# Processor-2.net
KiCad netlist of a schematic drawn in Altium Designer
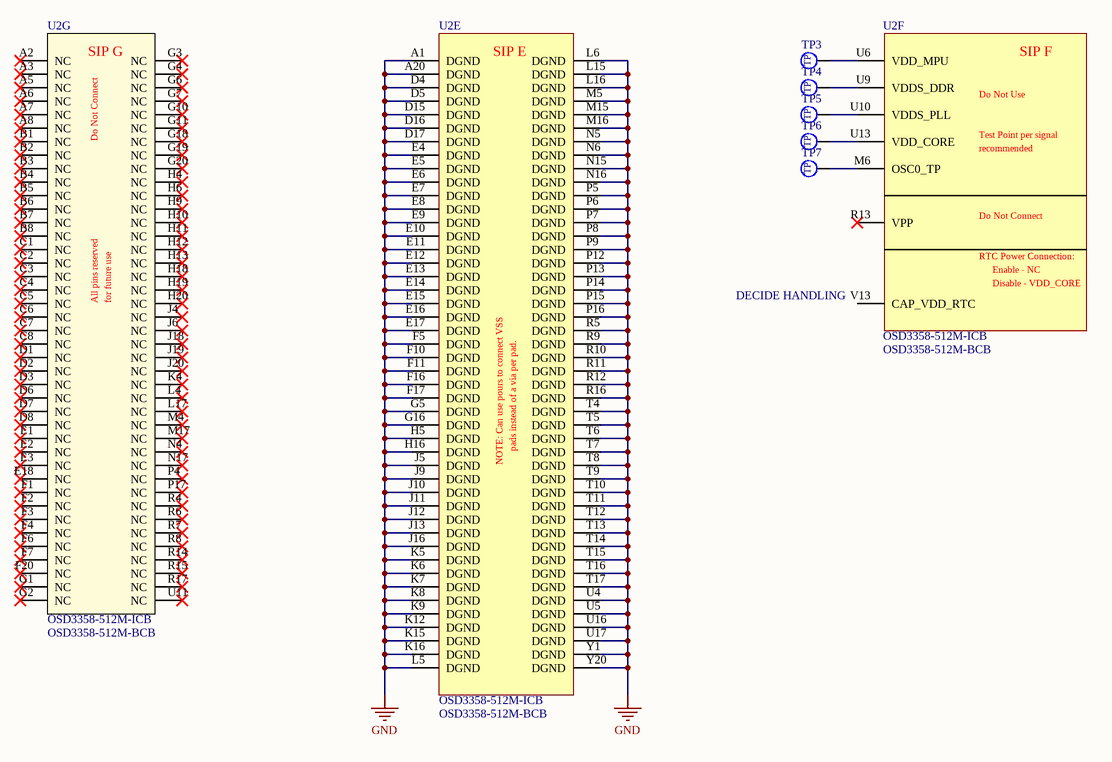
[diagram p0: Processor-2.SchDoc]

(export (version "E")
  (design (tool "Eeschema 10.0.6"))
  (components
    (comp (ref "TP3")
      (value "2.5mm_SMD_TestPoint")
      (footprint "2.5mm TestPoint")
      (libsource (lib "HAB_Components") (part "2.5mm_SMD_TestPoint"))
    )
    (comp (ref "TP4")
      (value "2.5mm_SMD_TestPoint")
      (footprint "2.5mm TestPoint")
      (libsource (lib "HAB_Components") (part "2.5mm_SMD_TestPoint"))
    )
    (comp (ref "TP5")
      (value "2.5mm_SMD_TestPoint")
      (footprint "2.5mm TestPoint")
      (libsource (lib "HAB_Components") (part "2.5mm_SMD_TestPoint"))
    )
    (comp (ref "TP6")
      (value "2.5mm_SMD_TestPoint")
      (footprint "2.5mm TestPoint")
      (libsource (lib "HAB_Components") (part "2.5mm_SMD_TestPoint"))
    )
    (comp (ref "TP7")
      (value "2.5mm_SMD_TestPoint")
      (footprint "2.5mm TestPoint")
      (libsource (lib "HAB_Components") (part "2.5mm_SMD_TestPoint"))
    )
    (comp (ref "U2")
      (value "OSD3358-512M-ICB")
      (footprint "BGA_20x20_400_1p27mm")
      (fields (field (name "MANUFACTURER") "Octavo Systems") (field (name "PARTNUMBER") "OSD3358-512M-BCB"))
      (libsource (lib "OctavoLib") (part "OSD3358-512M-ICB"))
    )
  )
  (nets
    (net (code "1") (name "GND") (class "Default")
      (node (ref "U2") (pin "A1") (pinfunction "DGND_A1") (pintype "power_in"))
      (node (ref "U2") (pin "A20") (pinfunction "DGND_A20") (pintype "power_in"))
      (node (ref "U2") (pin "D15") (pinfunction "DGND_D15") (pintype "power_in"))
      (node (ref "U2") (pin "D16") (pinfunction "DGND_D16") (pintype "power_in"))
      (node (ref "U2") (pin "D17") (pinfunction "DGND_D17") (pintype "power_in"))
      (node (ref "U2") (pin "D4") (pinfunction "DGND_D4") (pintype "power_in"))
      (node (ref "U2") (pin "D5") (pinfunction "DGND_D5") (pintype "power_in"))
      (node (ref "U2") (pin "E10") (pinfunction "DGND_E10") (pintype "power_in"))
      (node (ref "U2") (pin "E11") (pinfunction "DGND_E11") (pintype "power_in"))
      (node (ref "U2") (pin "E12") (pinfunction "DGND_E12") (pintype "power_in"))
      (node (ref "U2") (pin "E13") (pinfunction "DGND_E13") (pintype "power_in"))
      (node (ref "U2") (pin "E14") (pinfunction "DGND_E14") (pintype "power_in"))
      (node (ref "U2") (pin "E15") (pinfunction "DGND_E15") (pintype "power_in"))
      (node (ref "U2") (pin "E16") (pinfunction "DGND_E16") (pintype "power_in"))
      (node (ref "U2") (pin "E17") (pinfunction "DGND_E17") (pintype "power_in"))
      (node (ref "U2") (pin "E4") (pinfunction "DGND_E4") (pintype "power_in"))
      (node (ref "U2") (pin "E5") (pinfunction "DGND_E5") (pintype "power_in"))
      (node (ref "U2") (pin "E6") (pinfunction "DGND_E6") (pintype "power_in"))
      (node (ref "U2") (pin "E7") (pinfunction "DGND_E7") (pintype "power_in"))
      (node (ref "U2") (pin "E8") (pinfunction "DGND_E8") (pintype "power_in"))
      (node (ref "U2") (pin "E9") (pinfunction "DGND_E9") (pintype "power_in"))
      (node (ref "U2") (pin "F10") (pinfunction "DGND_F10") (pintype "power_in"))
      (node (ref "U2") (pin "F11") (pinfunction "DGND_F11") (pintype "power_in"))
      (node (ref "U2") (pin "F16") (pinfunction "DGND_F16") (pintype "power_in"))
      (node (ref "U2") (pin "F17") (pinfunction "DGND_F17") (pintype "power_in"))
      (node (ref "U2") (pin "F5") (pinfunction "DGND_F5") (pintype "power_in"))
      (node (ref "U2") (pin "G16") (pinfunction "DGND_G16") (pintype "power_in"))
      (node (ref "U2") (pin "G5") (pinfunction "DGND_G5") (pintype "power_in"))
      (node (ref "U2") (pin "H16") (pinfunction "DGND_H16") (pintype "power_in"))
      (node (ref "U2") (pin "H5") (pinfunction "DGND_H5") (pintype "power_in"))
      (node (ref "U2") (pin "J10") (pinfunction "DGND_J10") (pintype "power_in"))
      (node (ref "U2") (pin "J11") (pinfunction "DGND_J11") (pintype "power_in"))
      (node (ref "U2") (pin "J12") (pinfunction "DGND_J12") (pintype "power_in"))
      (node (ref "U2") (pin "J13") (pinfunction "DGND_J13") (pintype "power_in"))
      (node (ref "U2") (pin "J16") (pinfunction "DGND_J16") (pintype "power_in"))
      (node (ref "U2") (pin "J5") (pinfunction "DGND_J5") (pintype "power_in"))
      (node (ref "U2") (pin "J9") (pinfunction "DGND_J9") (pintype "power_in"))
      (node (ref "U2") (pin "K12") (pinfunction "DGND_K12") (pintype "power_in"))
      (node (ref "U2") (pin "K15") (pinfunction "DGND_K15") (pintype "power_in"))
      (node (ref "U2") (pin "K16") (pinfunction "DGND_K16") (pintype "power_in"))
      (node (ref "U2") (pin "K5") (pinfunction "DGND_K5") (pintype "power_in"))
      (node (ref "U2") (pin "K6") (pinfunction "DGND_K6") (pintype "power_in"))
      (node (ref "U2") (pin "K7") (pinfunction "DGND_K7") (pintype "power_in"))
      (node (ref "U2") (pin "K8") (pinfunction "DGND_K8") (pintype "power_in"))
      (node (ref "U2") (pin "K9") (pinfunction "DGND_K9") (pintype "power_in"))
      (node (ref "U2") (pin "L15") (pinfunction "DGND_L15") (pintype "power_in"))
      (node (ref "U2") (pin "L16") (pinfunction "DGND_L16") (pintype "power_in"))
      (node (ref "U2") (pin "L5") (pinfunction "DGND_L5") (pintype "power_in"))
      (node (ref "U2") (pin "L6") (pinfunction "DGND_L6") (pintype "power_in"))
      (node (ref "U2") (pin "M15") (pinfunction "DGND_M15") (pintype "power_in"))
      (node (ref "U2") (pin "M16") (pinfunction "DGND_M16") (pintype "power_in"))
      (node (ref "U2") (pin "M5") (pinfunction "DGND_M5") (pintype "power_in"))
      (node (ref "U2") (pin "N15") (pinfunction "DGND_N15") (pintype "power_in"))
      (node (ref "U2") (pin "N16") (pinfunction "DGND_N16") (pintype "power_in"))
      (node (ref "U2") (pin "N5") (pinfunction "DGND_N5") (pintype "power_in"))
      (node (ref "U2") (pin "N6") (pinfunction "DGND_N6") (pintype "power_in"))
      (node (ref "U2") (pin "P12") (pinfunction "DGND_P12") (pintype "power_in"))
      (node (ref "U2") (pin "P13") (pinfunction "DGND_P13") (pintype "power_in"))
      (node (ref "U2") (pin "P14") (pinfunction "DGND_P14") (pintype "power_in"))
      (node (ref "U2") (pin "P15") (pinfunction "DGND_P15") (pintype "power_in"))
      (node (ref "U2") (pin "P16") (pinfunction "DGND_P16") (pintype "power_in"))
      (node (ref "U2") (pin "P5") (pinfunction "DGND_P5") (pintype "power_in"))
      (node (ref "U2") (pin "P6") (pinfunction "DGND_P6") (pintype "power_in"))
      (node (ref "U2") (pin "P7") (pinfunction "DGND_P7") (pintype "power_in"))
      (node (ref "U2") (pin "P8") (pinfunction "DGND_P8") (pintype "power_in"))
      (node (ref "U2") (pin "P9") (pinfunction "DGND_P9") (pintype "power_in"))
      (node (ref "U2") (pin "R10") (pinfunction "DGND_R10") (pintype "power_in"))
      (node (ref "U2") (pin "R11") (pinfunction "DGND_R11") (pintype "power_in"))
      (node (ref "U2") (pin "R12") (pinfunction "DGND_R12") (pintype "power_in"))
      (node (ref "U2") (pin "R16") (pinfunction "DGND_R16") (pintype "power_in"))
      (node (ref "U2") (pin "R5") (pinfunction "DGND_R5") (pintype "power_in"))
      (node (ref "U2") (pin "R9") (pinfunction "DGND_R9") (pintype "power_in"))
      (node (ref "U2") (pin "T10") (pinfunction "DGND_T10") (pintype "power_in"))
      (node (ref "U2") (pin "T11") (pinfunction "DGND_T11") (pintype "power_in"))
      (node (ref "U2") (pin "T12") (pinfunction "DGND_T12") (pintype "power_in"))
      (node (ref "U2") (pin "T13") (pinfunction "DGND_T13") (pintype "power_in"))
      (node (ref "U2") (pin "T14") (pinfunction "DGND_T14") (pintype "power_in"))
      (node (ref "U2") (pin "T15") (pinfunction "DGND_T15") (pintype "power_in"))
      (node (ref "U2") (pin "T16") (pinfunction "DGND_T16") (pintype "power_in"))
      (node (ref "U2") (pin "T17") (pinfunction "DGND_T17") (pintype "power_in"))
      (node (ref "U2") (pin "T4") (pinfunction "DGND_T4") (pintype "power_in"))
      (node (ref "U2") (pin "T5") (pinfunction "DGND_T5") (pintype "power_in"))
      (node (ref "U2") (pin "T6") (pinfunction "DGND_T6") (pintype "power_in"))
      (node (ref "U2") (pin "T7") (pinfunction "DGND_T7") (pintype "power_in"))
      (node (ref "U2") (pin "T8") (pinfunction "DGND_T8") (pintype "power_in"))
      (node (ref "U2") (pin "T9") (pinfunction "DGND_T9") (pintype "power_in"))
      (node (ref "U2") (pin "U16") (pinfunction "DGND_U16") (pintype "power_in"))
      (node (ref "U2") (pin "U17") (pinfunction "DGND_U17") (pintype "power_in"))
      (node (ref "U2") (pin "U4") (pinfunction "DGND_U4") (pintype "power_in"))
      (node (ref "U2") (pin "U5") (pinfunction "DGND_U5") (pintype "power_in"))
      (node (ref "U2") (pin "Y1") (pinfunction "DGND_Y1") (pintype "power_in"))
      (node (ref "U2") (pin "Y20") (pinfunction "DGND_Y20") (pintype "power_in"))
    )
    (net (code "2") (name "Net-(U2F-OSC0_TP)") (class "Default")
      (node (ref "TP7") (pin "1") (pintype "passive"))
      (node (ref "U2") (pin "M6") (pinfunction "OSC0_TP_M6") (pintype "passive"))
    )
    (net (code "3") (name "Net-(U2F-VDDS_DDR)") (class "Default")
      (node (ref "TP4") (pin "1") (pintype "passive"))
      (node (ref "U2") (pin "U9") (pinfunction "VDDS_DDR_U9") (pintype "power_in"))
    )
    (net (code "4") (name "Net-(U2F-VDDS_PLL)") (class "Default")
      (node (ref "TP5") (pin "1") (pintype "passive"))
      (node (ref "U2") (pin "U10") (pinfunction "VDDS_PLL_U10") (pintype "power_in"))
    )
    (net (code "5") (name "Net-(U2F-VDD_CORE)") (class "Default")
      (node (ref "TP6") (pin "1") (pintype "passive"))
      (node (ref "U2") (pin "U13") (pinfunction "VDD_CORE_U13") (pintype "power_in"))
    )
    (net (code "6") (name "Net-(U2F-VDD_MPU)") (class "Default")
      (node (ref "TP3") (pin "1") (pintype "passive"))
      (node (ref "U2") (pin "U6") (pinfunction "VDD_MPU_U6") (pintype "power_in"))
    )
    (net (code "7") (name "unconnected-(U2F-CAP_VDD_RTC-PadV13)") (class "Default")
      (node (ref "U2") (pin "V13") (pinfunction "CAP_VDD_RTC_V13") (pintype "power_in"))
    )
    (net (code "8") (name "unconnected-(U2F-VPP-PadR13)") (class "Default")
      (node (ref "U2") (pin "R13") (pinfunction "VPP_R13") (pintype "power_in+no_connect"))
    )
    (net (code "9") (name "unconnected-(U2G-NC-PadA2)") (class "Default")
      (node (ref "U2") (pin "A2") (pinfunction "NC_A2") (pintype "passive+no_connect"))
    )
    (net (code "10") (name "unconnected-(U2G-NC-PadA3)") (class "Default")
      (node (ref "U2") (pin "A3") (pinfunction "NC_A3") (pintype "passive+no_connect"))
    )
    (net (code "11") (name "unconnected-(U2G-NC-PadA5)") (class "Default")
      (node (ref "U2") (pin "A5") (pinfunction "NC_A5") (pintype "passive+no_connect"))
    )
    (net (code "12") (name "unconnected-(U2G-NC-PadA6)") (class "Default")
      (node (ref "U2") (pin "A6") (pinfunction "NC_A6") (pintype "passive+no_connect"))
    )
    (net (code "13") (name "unconnected-(U2G-NC-PadA7)") (class "Default")
      (node (ref "U2") (pin "A7") (pinfunction "NC_A7") (pintype "passive+no_connect"))
    )
    (net (code "14") (name "unconnected-(U2G-NC-PadA8)") (class "Default")
      (node (ref "U2") (pin "A8") (pinfunction "NC_A8") (pintype "passive+no_connect"))
    )
    (net (code "15") (name "unconnected-(U2G-NC-PadB1)") (class "Default")
      (node (ref "U2") (pin "B1") (pinfunction "NC_B1") (pintype "passive+no_connect"))
    )
    (net (code "16") (name "unconnected-(U2G-NC-PadB2)") (class "Default")
      (node (ref "U2") (pin "B2") (pinfunction "NC_B2") (pintype "passive+no_connect"))
    )
    (net (code "17") (name "unconnected-(U2G-NC-PadB3)") (class "Default")
      (node (ref "U2") (pin "B3") (pinfunction "NC_B3") (pintype "passive+no_connect"))
    )
    (net (code "18") (name "unconnected-(U2G-NC-PadB4)") (class "Default")
      (node (ref "U2") (pin "B4") (pinfunction "NC_B4") (pintype "passive+no_connect"))
    )
    (net (code "19") (name "unconnected-(U2G-NC-PadB5)") (class "Default")
      (node (ref "U2") (pin "B5") (pinfunction "NC_B5") (pintype "passive+no_connect"))
    )
    (net (code "20") (name "unconnected-(U2G-NC-PadB6)") (class "Default")
      (node (ref "U2") (pin "B6") (pinfunction "NC_B6") (pintype "passive+no_connect"))
    )
    (net (code "21") (name "unconnected-(U2G-NC-PadB7)") (class "Default")
      (node (ref "U2") (pin "B7") (pinfunction "NC_B7") (pintype "passive+no_connect"))
    )
    (net (code "22") (name "unconnected-(U2G-NC-PadB8)") (class "Default")
      (node (ref "U2") (pin "B8") (pinfunction "NC_B8") (pintype "passive+no_connect"))
    )
    (net (code "23") (name "unconnected-(U2G-NC-PadC1)") (class "Default")
      (node (ref "U2") (pin "C1") (pinfunction "NC_C1") (pintype "passive+no_connect"))
    )
    (net (code "24") (name "unconnected-(U2G-NC-PadC2)") (class "Default")
      (node (ref "U2") (pin "C2") (pinfunction "NC_C2") (pintype "passive+no_connect"))
    )
    (net (code "25") (name "unconnected-(U2G-NC-PadC3)") (class "Default")
      (node (ref "U2") (pin "C3") (pinfunction "NC_C3") (pintype "passive+no_connect"))
    )
    (net (code "26") (name "unconnected-(U2G-NC-PadC4)") (class "Default")
      (node (ref "U2") (pin "C4") (pinfunction "NC_C4") (pintype "passive+no_connect"))
    )
    (net (code "27") (name "unconnected-(U2G-NC-PadC5)") (class "Default")
      (node (ref "U2") (pin "C5") (pinfunction "NC_C5") (pintype "passive+no_connect"))
    )
    (net (code "28") (name "unconnected-(U2G-NC-PadC6)") (class "Default")
      (node (ref "U2") (pin "C6") (pinfunction "NC_C6") (pintype "passive+no_connect"))
    )
    (net (code "29") (name "unconnected-(U2G-NC-PadC7)") (class "Default")
      (node (ref "U2") (pin "C7") (pinfunction "NC_C7") (pintype "passive+no_connect"))
    )
    (net (code "30") (name "unconnected-(U2G-NC-PadC8)") (class "Default")
      (node (ref "U2") (pin "C8") (pinfunction "NC_C8") (pintype "passive+no_connect"))
    )
    (net (code "31") (name "unconnected-(U2G-NC-PadD1)") (class "Default")
      (node (ref "U2") (pin "D1") (pinfunction "NC_D1") (pintype "passive+no_connect"))
    )
    (net (code "32") (name "unconnected-(U2G-NC-PadD2)") (class "Default")
      (node (ref "U2") (pin "D2") (pinfunction "NC_D2") (pintype "passive+no_connect"))
    )
    (net (code "33") (name "unconnected-(U2G-NC-PadD3)") (class "Default")
      (node (ref "U2") (pin "D3") (pinfunction "NC_D3") (pintype "passive+no_connect"))
    )
    (net (code "34") (name "unconnected-(U2G-NC-PadD6)") (class "Default")
      (node (ref "U2") (pin "D6") (pinfunction "NC_D6") (pintype "passive+no_connect"))
    )
    (net (code "35") (name "unconnected-(U2G-NC-PadD7)") (class "Default")
      (node (ref "U2") (pin "D7") (pinfunction "NC_D7") (pintype "passive+no_connect"))
    )
    (net (code "36") (name "unconnected-(U2G-NC-PadD8)") (class "Default")
      (node (ref "U2") (pin "D8") (pinfunction "NC_D8") (pintype "passive+no_connect"))
    )
    (net (code "37") (name "unconnected-(U2G-NC-PadE1)") (class "Default")
      (node (ref "U2") (pin "E1") (pinfunction "NC_E1") (pintype "passive+no_connect"))
    )
    (net (code "38") (name "unconnected-(U2G-NC-PadE2)") (class "Default")
      (node (ref "U2") (pin "E2") (pinfunction "NC_E2") (pintype "passive+no_connect"))
    )
    (net (code "39") (name "unconnected-(U2G-NC-PadE3)") (class "Default")
      (node (ref "U2") (pin "E3") (pinfunction "NC_E3") (pintype "passive+no_connect"))
    )
    (net (code "40") (name "unconnected-(U2G-NC-PadE18)") (class "Default")
      (node (ref "U2") (pin "E18") (pinfunction "NC_E18") (pintype "passive+no_connect"))
    )
    (net (code "41") (name "unconnected-(U2G-NC-PadF1)") (class "Default")
      (node (ref "U2") (pin "F1") (pinfunction "NC_F1") (pintype "passive+no_connect"))
    )
    (net (code "42") (name "unconnected-(U2G-NC-PadF2)") (class "Default")
      (node (ref "U2") (pin "F2") (pinfunction "NC_F2") (pintype "passive+no_connect"))
    )
    (net (code "43") (name "unconnected-(U2G-NC-PadF3)") (class "Default")
      (node (ref "U2") (pin "F3") (pinfunction "NC_F3") (pintype "passive+no_connect"))
    )
    (net (code "44") (name "unconnected-(U2G-NC-PadF4)") (class "Default")
      (node (ref "U2") (pin "F4") (pinfunction "NC_F4") (pintype "passive+no_connect"))
    )
    (net (code "45") (name "unconnected-(U2G-NC-PadF6)") (class "Default")
      (node (ref "U2") (pin "F6") (pinfunction "NC_F6") (pintype "power_in+no_connect"))
    )
    (net (code "46") (name "unconnected-(U2G-NC-PadF7)") (class "Default")
      (node (ref "U2") (pin "F7") (pinfunction "NC_F7") (pintype "power_in+no_connect"))
    )
    (net (code "47") (name "unconnected-(U2G-NC-PadF20)") (class "Default")
      (node (ref "U2") (pin "F20") (pinfunction "NC_F20") (pintype "passive+no_connect"))
    )
    (net (code "48") (name "unconnected-(U2G-NC-PadG1)") (class "Default")
      (node (ref "U2") (pin "G1") (pinfunction "NC_G1") (pintype "passive+no_connect"))
    )
    (net (code "49") (name "unconnected-(U2G-NC-PadG2)") (class "Default")
      (node (ref "U2") (pin "G2") (pinfunction "NC_G2") (pintype "passive+no_connect"))
    )
    (net (code "50") (name "unconnected-(U2G-NC-PadG3)") (class "Default")
      (node (ref "U2") (pin "G3") (pinfunction "NC_G3") (pintype "passive+no_connect"))
    )
    (net (code "51") (name "unconnected-(U2G-NC-PadG4)") (class "Default")
      (node (ref "U2") (pin "G4") (pinfunction "NC_G4") (pintype "passive+no_connect"))
    )
    (net (code "52") (name "unconnected-(U2G-NC-PadG6)") (class "Default")
      (node (ref "U2") (pin "G6") (pinfunction "NC_G6") (pintype "power_in+no_connect"))
    )
    (net (code "53") (name "unconnected-(U2G-NC-PadG7)") (class "Default")
      (node (ref "U2") (pin "G7") (pinfunction "NC_G7") (pintype "power_in+no_connect"))
    )
    (net (code "54") (name "unconnected-(U2G-NC-PadG10)") (class "Default")
      (node (ref "U2") (pin "G10") (pinfunction "NC_G10") (pintype "passive+no_connect"))
    )
    (net (code "55") (name "unconnected-(U2G-NC-PadG11)") (class "Default")
      (node (ref "U2") (pin "G11") (pinfunction "NC_G11") (pintype "passive+no_connect"))
    )
    (net (code "56") (name "unconnected-(U2G-NC-PadG18)") (class "Default")
      (node (ref "U2") (pin "G18") (pinfunction "NC_G18") (pintype "passive+no_connect"))
    )
    (net (code "57") (name "unconnected-(U2G-NC-PadG19)") (class "Default")
      (node (ref "U2") (pin "G19") (pinfunction "NC_G19") (pintype "passive+no_connect"))
    )
    (net (code "58") (name "unconnected-(U2G-NC-PadG20)") (class "Default")
      (node (ref "U2") (pin "G20") (pinfunction "NC_G20") (pintype "passive+no_connect"))
    )
    (net (code "59") (name "unconnected-(U2G-NC-PadH4)") (class "Default")
      (node (ref "U2") (pin "H4") (pinfunction "NC_H4") (pintype "passive+no_connect"))
    )
    (net (code "60") (name "unconnected-(U2G-NC-PadH6)") (class "Default")
      (node (ref "U2") (pin "H6") (pinfunction "NC_H6") (pintype "passive+no_connect"))
    )
    (net (code "61") (name "unconnected-(U2G-NC-PadH9)") (class "Default")
      (node (ref "U2") (pin "H9") (pinfunction "NC_H9") (pintype "passive+no_connect"))
    )
    (net (code "62") (name "unconnected-(U2G-NC-PadH10)") (class "Default")
      (node (ref "U2") (pin "H10") (pinfunction "NC_H10") (pintype "passive+no_connect"))
    )
    (net (code "63") (name "unconnected-(U2G-NC-PadH11)") (class "Default")
      (node (ref "U2") (pin "H11") (pinfunction "NC_H11") (pintype "passive+no_connect"))
    )
    (net (code "64") (name "unconnected-(U2G-NC-PadH12)") (class "Default")
      (node (ref "U2") (pin "H12") (pinfunction "NC_H12") (pintype "passive+no_connect"))
    )
    (net (code "65") (name "unconnected-(U2G-NC-PadH13)") (class "Default")
      (node (ref "U2") (pin "H13") (pinfunction "NC_H13") (pintype "passive+no_connect"))
    )
    (net (code "66") (name "unconnected-(U2G-NC-PadH18)") (class "Default")
      (node (ref "U2") (pin "H18") (pinfunction "NC_H18") (pintype "passive+no_connect"))
    )
    (net (code "67") (name "unconnected-(U2G-NC-PadH19)") (class "Default")
      (node (ref "U2") (pin "H19") (pinfunction "NC_H19") (pintype "passive+no_connect"))
    )
    (net (code "68") (name "unconnected-(U2G-NC-PadH20)") (class "Default")
      (node (ref "U2") (pin "H20") (pinfunction "NC_H20") (pintype "passive+no_connect"))
    )
    (net (code "69") (name "unconnected-(U2G-NC-PadJ4)") (class "Default")
      (node (ref "U2") (pin "J4") (pinfunction "NC_J4") (pintype "passive+no_connect"))
    )
    (net (code "70") (name "unconnected-(U2G-NC-PadJ6)") (class "Default")
      (node (ref "U2") (pin "J6") (pinfunction "NC_J6") (pintype "passive+no_connect"))
    )
    (net (code "71") (name "unconnected-(U2G-NC-PadJ18)") (class "Default")
      (node (ref "U2") (pin "J18") (pinfunction "NC_J18") (pintype "passive+no_connect"))
    )
    (net (code "72") (name "unconnected-(U2G-NC-PadJ19)") (class "Default")
      (node (ref "U2") (pin "J19") (pinfunction "NC_J19") (pintype "passive+no_connect"))
    )
    (net (code "73") (name "unconnected-(U2G-NC-PadJ20)") (class "Default")
      (node (ref "U2") (pin "J20") (pinfunction "NC_J20") (pintype "passive+no_connect"))
    )
    (net (code "74") (name "unconnected-(U2G-NC-PadK4)") (class "Default")
      (node (ref "U2") (pin "K4") (pinfunction "NC_K4") (pintype "passive+no_connect"))
    )
    (net (code "75") (name "unconnected-(U2G-NC-PadL4)") (class "Default")
      (node (ref "U2") (pin "L4") (pinfunction "NC_L4") (pintype "passive+no_connect"))
    )
    (net (code "76") (name "unconnected-(U2G-NC-PadL17)") (class "Default")
      (node (ref "U2") (pin "L17") (pinfunction "NC_L17") (pintype "passive+no_connect"))
    )
    (net (code "77") (name "unconnected-(U2G-NC-PadM4)") (class "Default")
      (node (ref "U2") (pin "M4") (pinfunction "NC_M4") (pintype "passive+no_connect"))
    )
    (net (code "78") (name "unconnected-(U2G-NC-PadM17)") (class "Default")
      (node (ref "U2") (pin "M17") (pinfunction "NC_M17") (pintype "passive+no_connect"))
    )
    (net (code "79") (name "unconnected-(U2G-NC-PadN4)") (class "Default")
      (node (ref "U2") (pin "N4") (pinfunction "NC_N4") (pintype "passive+no_connect"))
    )
    (net (code "80") (name "unconnected-(U2G-NC-PadN17)") (class "Default")
      (node (ref "U2") (pin "N17") (pinfunction "NC_N17") (pintype "passive+no_connect"))
    )
    (net (code "81") (name "unconnected-(U2G-NC-PadP4)") (class "Default")
      (node (ref "U2") (pin "P4") (pinfunction "NC_P4") (pintype "passive+no_connect"))
    )
    (net (code "82") (name "unconnected-(U2G-NC-PadP17)") (class "Default")
      (node (ref "U2") (pin "P17") (pinfunction "NC_P17") (pintype "passive+no_connect"))
    )
    (net (code "83") (name "unconnected-(U2G-NC-PadR4)") (class "Default")
      (node (ref "U2") (pin "R4") (pinfunction "NC_R4") (pintype "passive+no_connect"))
    )
    (net (code "84") (name "unconnected-(U2G-NC-PadR6)") (class "Default")
      (node (ref "U2") (pin "R6") (pinfunction "NC_R6") (pintype "passive+no_connect"))
    )
    (net (code "85") (name "unconnected-(U2G-NC-PadR7)") (class "Default")
      (node (ref "U2") (pin "R7") (pinfunction "NC_R7") (pintype "passive+no_connect"))
    )
    (net (code "86") (name "unconnected-(U2G-NC-PadR8)") (class "Default")
      (node (ref "U2") (pin "R8") (pinfunction "NC_R8") (pintype "power_in+no_connect"))
    )
    (net (code "87") (name "unconnected-(U2G-NC-PadR14)") (class "Default")
      (node (ref "U2") (pin "R14") (pinfunction "NC_R14") (pintype "passive+no_connect"))
    )
    (net (code "88") (name "unconnected-(U2G-NC-PadR15)") (class "Default")
      (node (ref "U2") (pin "R15") (pinfunction "NC_R15") (pintype "passive+no_connect"))
    )
    (net (code "89") (name "unconnected-(U2G-NC-PadR17)") (class "Default")
      (node (ref "U2") (pin "R17") (pinfunction "NC_R17") (pintype "passive+no_connect"))
    )
    (net (code "90") (name "unconnected-(U2G-NC-PadU11)") (class "Default")
      (node (ref "U2") (pin "U11") (pinfunction "NC_U11") (pintype "passive+no_connect"))
    )
  )
)
